# ControlPanel.net
KiCad netlist of a schematic drawn in Altium Designer
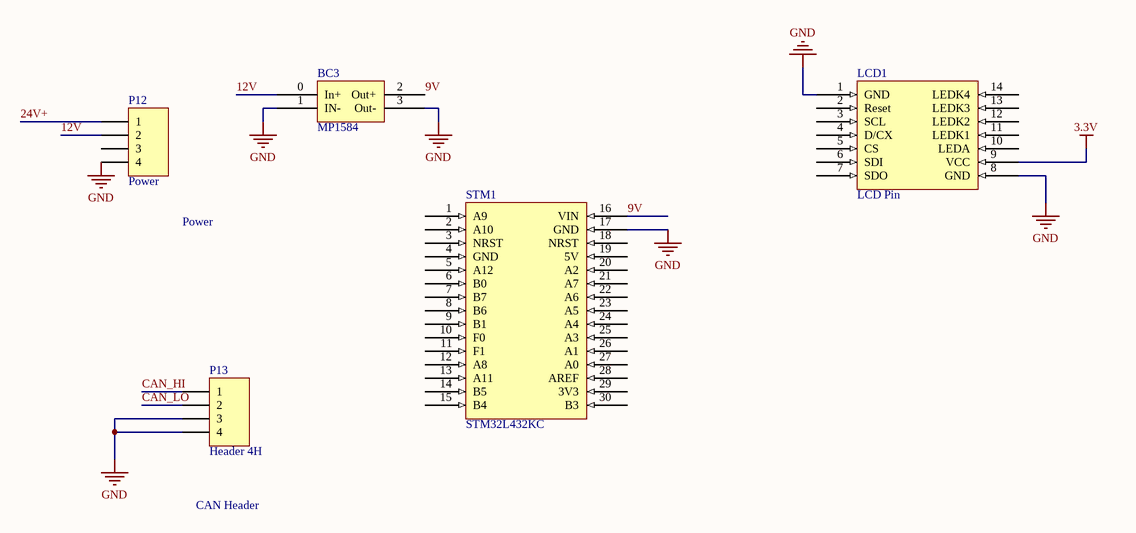
[diagram p0: ControlPanel.SchDoc]

(export (version "E")
  (design (tool "Eeschema 10.0.6"))
  (components
    (comp (ref "BC3") (value "MP1584") (libsource (lib "Pod3") (part "MP1584")))
    (comp (ref "LCD1")
      (value "LCD Pin")
      (footprint "LCD Display Header")
      (libsource (lib "Pod3") (part "LCD Pin"))
    )
    (comp (ref "P12")
      (value "Power")
      (footprint "HDR1X4")
      (description "Header, 4-Pin")
      (fields (field (name "PUBLISHER") "Altium Limited"))
      (libsource (lib "Miscellaneous Connectors") (part "Header 4"))
    )
    (comp (ref "P13")
      (value "Header 4H")
      (footprint "HDR1X4H")
      (description "Header, 4-Pin, Right Angle")
      (fields (field (name "PUBLISHER") "Altium Limited"))
      (libsource (lib "Miscellaneous Connectors") (part "Header 4H"))
    )
    (comp (ref "STM1") (value "STM32L432KC") (libsource (lib "Pod3") (part "STMF303K8")))
  )
  (nets
    (net (code "1") (name "/9V") (class "Default")
      (node (ref "BC3") (pin "2") (pinfunction "Out+_2") (pintype "passive"))
      (node (ref "STM1") (pin "16") (pinfunction "VIN_16") (pintype "input"))
    )
    (net (code "2") (name "/12V") (class "Default")
      (node (ref "BC3") (pin "0") (pinfunction "In+_0") (pintype "passive"))
      (node (ref "P12") (pin "2") (pinfunction "2_2") (pintype "passive"))
    )
    (net (code "3") (name "/24V+") (class "Default")
      (node (ref "P12") (pin "1") (pinfunction "1_1") (pintype "passive"))
    )
    (net (code "4") (name "/CAN_HI") (class "Default")
      (node (ref "P13") (pin "1") (pinfunction "1_1") (pintype "passive"))
    )
    (net (code "5") (name "/CAN_LO") (class "Default")
      (node (ref "P13") (pin "2") (pinfunction "2_2") (pintype "passive"))
    )
    (net (code "6") (name "3.3V") (class "Default")
      (node (ref "LCD1") (pin "9") (pinfunction "VCC_9") (pintype "input"))
    )
    (net (code "7") (name "GND") (class "Default")
      (node (ref "BC3") (pin "1") (pinfunction "IN-_1") (pintype "passive"))
      (node (ref "BC3") (pin "3") (pinfunction "Out-_3") (pintype "passive"))
      (node (ref "LCD1") (pin "1") (pinfunction "GND_1") (pintype "input"))
      (node (ref "LCD1") (pin "8") (pinfunction "GND_8") (pintype "input"))
      (node (ref "P12") (pin "4") (pinfunction "4_4") (pintype "passive"))
      (node (ref "P13") (pin "3") (pinfunction "3_3") (pintype "passive"))
      (node (ref "P13") (pin "4") (pinfunction "4_4") (pintype "passive"))
      (node (ref "STM1") (pin "17") (pinfunction "GND_17") (pintype "input"))
    )
    (net (code "8") (name "unconnected-(LCD1-CS-Pad5)") (class "Default")
      (node (ref "LCD1") (pin "5") (pinfunction "CS_5") (pintype "input"))
    )
    (net (code "9") (name "unconnected-(LCD1-D{slash}CX-Pad4)") (class "Default")
      (node (ref "LCD1") (pin "4") (pinfunction "D/CX_4") (pintype "input"))
    )
    (net (code "10") (name "unconnected-(LCD1-LEDA-Pad10)") (class "Default")
      (node (ref "LCD1") (pin "10") (pinfunction "LEDA_10") (pintype "input"))
    )
    (net (code "11") (name "unconnected-(LCD1-LEDK1-Pad11)") (class "Default")
      (node (ref "LCD1") (pin "11") (pinfunction "LEDK1_11") (pintype "input"))
    )
    (net (code "12") (name "unconnected-(LCD1-LEDK2-Pad12)") (class "Default")
      (node (ref "LCD1") (pin "12") (pinfunction "LEDK2_12") (pintype "input"))
    )
    (net (code "13") (name "unconnected-(LCD1-LEDK3-Pad13)") (class "Default")
      (node (ref "LCD1") (pin "13") (pinfunction "LEDK3_13") (pintype "input"))
    )
    (net (code "14") (name "unconnected-(LCD1-LEDK4-Pad14)") (class "Default")
      (node (ref "LCD1") (pin "14") (pinfunction "LEDK4_14") (pintype "input"))
    )
    (net (code "15") (name "unconnected-(LCD1-Reset-Pad2)") (class "Default")
      (node (ref "LCD1") (pin "2") (pinfunction "Reset_2") (pintype "input"))
    )
    (net (code "16") (name "unconnected-(LCD1-SCL-Pad3)") (class "Default")
      (node (ref "LCD1") (pin "3") (pinfunction "SCL_3") (pintype "input"))
    )
    (net (code "17") (name "unconnected-(LCD1-SDI-Pad6)") (class "Default")
      (node (ref "LCD1") (pin "6") (pinfunction "SDI_6") (pintype "input"))
    )
    (net (code "18") (name "unconnected-(LCD1-SDO-Pad7)") (class "Default")
      (node (ref "LCD1") (pin "7") (pinfunction "SDO_7") (pintype "input"))
    )
    (net (code "19") (name "unconnected-(P12-Pad3)") (class "Default")
      (node (ref "P12") (pin "3") (pinfunction "3_3") (pintype "passive"))
    )
    (net (code "20") (name "unconnected-(STM1-3V3-Pad29)") (class "Default")
      (node (ref "STM1") (pin "29") (pinfunction "3V3_29") (pintype "input"))
    )
    (net (code "21") (name "unconnected-(STM1-5V-Pad19)") (class "Default")
      (node (ref "STM1") (pin "19") (pinfunction "5V_19") (pintype "input"))
    )
    (net (code "22") (name "unconnected-(STM1-A0-Pad27)") (class "Default")
      (node (ref "STM1") (pin "27") (pinfunction "A0_27") (pintype "input"))
    )
    (net (code "23") (name "unconnected-(STM1-A1-Pad26)") (class "Default")
      (node (ref "STM1") (pin "26") (pinfunction "A1_26") (pintype "input"))
    )
    (net (code "24") (name "unconnected-(STM1-A2-Pad20)") (class "Default")
      (node (ref "STM1") (pin "20") (pinfunction "A2_20") (pintype "input"))
    )
    (net (code "25") (name "unconnected-(STM1-A3-Pad25)") (class "Default")
      (node (ref "STM1") (pin "25") (pinfunction "A3_25") (pintype "input"))
    )
    (net (code "26") (name "unconnected-(STM1-A4-Pad24)") (class "Default")
      (node (ref "STM1") (pin "24") (pinfunction "A4_24") (pintype "input"))
    )
    (net (code "27") (name "unconnected-(STM1-A5-Pad23)") (class "Default")
      (node (ref "STM1") (pin "23") (pinfunction "A5_23") (pintype "input"))
    )
    (net (code "28") (name "unconnected-(STM1-A6-Pad22)") (class "Default")
      (node (ref "STM1") (pin "22") (pinfunction "A6_22") (pintype "input"))
    )
    (net (code "29") (name "unconnected-(STM1-A7-Pad21)") (class "Default")
      (node (ref "STM1") (pin "21") (pinfunction "A7_21") (pintype "input"))
    )
    (net (code "30") (name "unconnected-(STM1-A8-Pad12)") (class "Default")
      (node (ref "STM1") (pin "12") (pinfunction "A8_12") (pintype "input"))
    )
    (net (code "31") (name "unconnected-(STM1-A9-Pad1)") (class "Default")
      (node (ref "STM1") (pin "1") (pinfunction "A9_1") (pintype "input"))
    )
    (net (code "32") (name "unconnected-(STM1-A10-Pad2)") (class "Default")
      (node (ref "STM1") (pin "2") (pinfunction "A10_2") (pintype "input"))
    )
    (net (code "33") (name "unconnected-(STM1-A11-Pad13)") (class "Default")
      (node (ref "STM1") (pin "13") (pinfunction "A11_13") (pintype "input"))
    )
    (net (code "34") (name "unconnected-(STM1-A12-Pad5)") (class "Default")
      (node (ref "STM1") (pin "5") (pinfunction "A12_5") (pintype "input"))
    )
    (net (code "35") (name "unconnected-(STM1-AREF-Pad28)") (class "Default")
      (node (ref "STM1") (pin "28") (pinfunction "AREF_28") (pintype "input"))
    )
    (net (code "36") (name "unconnected-(STM1-B0-Pad6)") (class "Default")
      (node (ref "STM1") (pin "6") (pinfunction "B0_6") (pintype "input"))
    )
    (net (code "37") (name "unconnected-(STM1-B1-Pad9)") (class "Default")
      (node (ref "STM1") (pin "9") (pinfunction "B1_9") (pintype "input"))
    )
    (net (code "38") (name "unconnected-(STM1-B3-Pad30)") (class "Default")
      (node (ref "STM1") (pin "30") (pinfunction "B3_30") (pintype "input"))
    )
    (net (code "39") (name "unconnected-(STM1-B4-Pad15)") (class "Default")
      (node (ref "STM1") (pin "15") (pinfunction "B4_15") (pintype "input"))
    )
    (net (code "40") (name "unconnected-(STM1-B5-Pad14)") (class "Default")
      (node (ref "STM1") (pin "14") (pinfunction "B5_14") (pintype "input"))
    )
    (net (code "41") (name "unconnected-(STM1-B6-Pad8)") (class "Default")
      (node (ref "STM1") (pin "8") (pinfunction "B6_8") (pintype "input"))
    )
    (net (code "42") (name "unconnected-(STM1-B7-Pad7)") (class "Default")
      (node (ref "STM1") (pin "7") (pinfunction "B7_7") (pintype "input"))
    )
    (net (code "43") (name "unconnected-(STM1-F0-Pad10)") (class "Default")
      (node (ref "STM1") (pin "10") (pinfunction "F0_10") (pintype "input"))
    )
    (net (code "44") (name "unconnected-(STM1-F1-Pad11)") (class "Default")
      (node (ref "STM1") (pin "11") (pinfunction "F1_11") (pintype "input"))
    )
    (net (code "45") (name "unconnected-(STM1-GND-Pad4)") (class "Default")
      (node (ref "STM1") (pin "4") (pinfunction "GND_4") (pintype "input"))
    )
    (net (code "46") (name "unconnected-(STM1-NRST-Pad3)") (class "Default")
      (node (ref "STM1") (pin "3") (pinfunction "NRST_3") (pintype "input"))
    )
    (net (code "47") (name "unconnected-(STM1-NRST-Pad18)") (class "Default")
      (node (ref "STM1") (pin "18") (pinfunction "NRST_18") (pintype "input"))
    )
  )
)
